# SCFschem.net
KiCad netlist of a schematic drawn in EAGLE
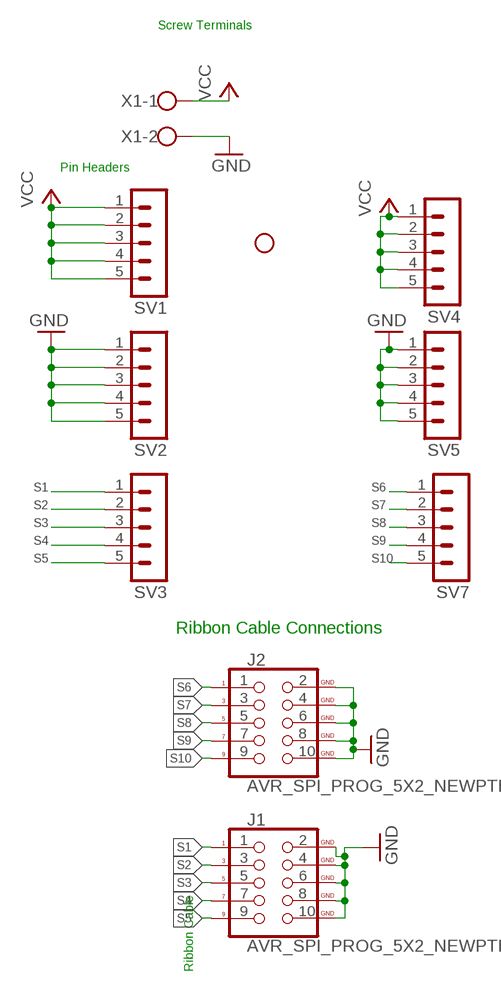
[diagram p0: schematic, sheet 1]

(export (version "E")
  (design (tool "Eeschema 10.0.6"))
  (components
    (comp (ref "H1")
      (value "STAND-OFF")
      (footprint "eagle-import:STAND-OFF")
      (libsource (lib "eagle-import") (part "STAND-OFF"))
    )
    (comp (ref "J1")
      (value "AVR_SPI_PROG_5X2_NEWPTH2")
      (footprint "eagle-import:2X5-SHROUDED")
      (libsource (lib "eagle-import") (part "AVR_SPI_PROG_5X2_NEWPTH2"))
    )
    (comp (ref "J2")
      (value "AVR_SPI_PROG_5X2_NEWPTH2")
      (footprint "eagle-import:2X5-SHROUDED")
      (libsource (lib "eagle-import") (part "AVR_SPI_PROG_5X2_NEWPTH2"))
    )
    (comp (ref "SV1")
      (value "MA05-1")
      (footprint "eagle-import:MA05-1")
      (libsource (lib "eagle-import") (part "MA05-1"))
    )
    (comp (ref "SV2")
      (value "MA05-1")
      (footprint "eagle-import:MA05-1")
      (libsource (lib "eagle-import") (part "MA05-1"))
    )
    (comp (ref "SV3")
      (value "MA05-1")
      (footprint "eagle-import:MA05-1")
      (libsource (lib "eagle-import") (part "MA05-1"))
    )
    (comp (ref "SV4")
      (value "MA05-1")
      (footprint "eagle-import:MA05-1")
      (libsource (lib "eagle-import") (part "MA05-1"))
    )
    (comp (ref "SV5")
      (value "MA05-1")
      (footprint "eagle-import:MA05-1")
      (libsource (lib "eagle-import") (part "MA05-1"))
    )
    (comp (ref "SV7")
      (value "MA05-1")
      (footprint "eagle-import:MA05-1")
      (libsource (lib "eagle-import") (part "MA05-1"))
    )
    (comp (ref "X1")
      (value "1X02_5MM_SCREW")
      (footprint "eagle-import:W237-102")
      (fields (field (name "MPN") "237-102"))
      (libsource (lib "eagle-import") (part "1X02_5MM_SCREW"))
    )
  )
  (nets
    (net (code "1") (name "GND") (class "Default")
      (node (ref "J1") (pin "10") (pinfunction "GND_10") (pintype "power_in"))
      (node (ref "J1") (pin "2") (pinfunction "GND_2") (pintype "power_in"))
      (node (ref "J1") (pin "4") (pinfunction "GND_4") (pintype "power_in"))
      (node (ref "J1") (pin "6") (pinfunction "GND_6") (pintype "power_in"))
      (node (ref "J1") (pin "8") (pinfunction "GND_8") (pintype "power_in"))
      (node (ref "J2") (pin "10") (pinfunction "GND_10") (pintype "power_in"))
      (node (ref "J2") (pin "2") (pinfunction "GND_2") (pintype "power_in"))
      (node (ref "J2") (pin "4") (pinfunction "GND_4") (pintype "power_in"))
      (node (ref "J2") (pin "6") (pinfunction "GND_6") (pintype "power_in"))
      (node (ref "J2") (pin "8") (pinfunction "GND_8") (pintype "power_in"))
      (node (ref "SV2") (pin "1") (pinfunction "1_1") (pintype "passive"))
      (node (ref "SV2") (pin "2") (pinfunction "2_2") (pintype "passive"))
      (node (ref "SV2") (pin "3") (pinfunction "3_3") (pintype "passive"))
      (node (ref "SV2") (pin "4") (pinfunction "4_4") (pintype "passive"))
      (node (ref "SV2") (pin "5") (pinfunction "5_5") (pintype "passive"))
      (node (ref "SV5") (pin "1") (pinfunction "1_1") (pintype "passive"))
      (node (ref "SV5") (pin "2") (pinfunction "2_2") (pintype "passive"))
      (node (ref "SV5") (pin "3") (pinfunction "3_3") (pintype "passive"))
      (node (ref "SV5") (pin "4") (pinfunction "4_4") (pintype "passive"))
      (node (ref "SV5") (pin "5") (pinfunction "5_5") (pintype "passive"))
      (node (ref "X1") (pin "2") (pinfunction "KL_2") (pintype "passive"))
    )
    (net (code "2") (name "S1") (class "Default")
      (node (ref "J1") (pin "1") (pinfunction "1_1") (pintype "passive"))
      (node (ref "SV3") (pin "1") (pinfunction "1_1") (pintype "passive"))
    )
    (net (code "3") (name "S2") (class "Default")
      (node (ref "J1") (pin "3") (pinfunction "3_3") (pintype "passive"))
      (node (ref "SV3") (pin "2") (pinfunction "2_2") (pintype "passive"))
    )
    (net (code "4") (name "S3") (class "Default")
      (node (ref "J1") (pin "5") (pinfunction "5_5") (pintype "passive"))
      (node (ref "SV3") (pin "3") (pinfunction "3_3") (pintype "passive"))
    )
    (net (code "5") (name "S4") (class "Default")
      (node (ref "J1") (pin "7") (pinfunction "7_7") (pintype "passive"))
      (node (ref "SV3") (pin "4") (pinfunction "4_4") (pintype "passive"))
    )
    (net (code "6") (name "S5") (class "Default")
      (node (ref "J1") (pin "9") (pinfunction "9_9") (pintype "passive"))
      (node (ref "SV3") (pin "5") (pinfunction "5_5") (pintype "passive"))
    )
    (net (code "7") (name "S6") (class "Default")
      (node (ref "J2") (pin "1") (pinfunction "1_1") (pintype "passive"))
      (node (ref "SV7") (pin "1") (pinfunction "1_1") (pintype "passive"))
    )
    (net (code "8") (name "S7") (class "Default")
      (node (ref "J2") (pin "3") (pinfunction "3_3") (pintype "passive"))
      (node (ref "SV7") (pin "2") (pinfunction "2_2") (pintype "passive"))
    )
    (net (code "9") (name "S8") (class "Default")
      (node (ref "J2") (pin "5") (pinfunction "5_5") (pintype "passive"))
      (node (ref "SV7") (pin "3") (pinfunction "3_3") (pintype "passive"))
    )
    (net (code "10") (name "S9") (class "Default")
      (node (ref "J2") (pin "7") (pinfunction "7_7") (pintype "passive"))
      (node (ref "SV7") (pin "4") (pinfunction "4_4") (pintype "passive"))
    )
    (net (code "11") (name "S10") (class "Default")
      (node (ref "J2") (pin "9") (pinfunction "9_9") (pintype "passive"))
      (node (ref "SV7") (pin "5") (pinfunction "5_5") (pintype "passive"))
    )
    (net (code "12") (name "VCC") (class "Default")
      (node (ref "SV1") (pin "1") (pinfunction "1_1") (pintype "passive"))
      (node (ref "SV1") (pin "2") (pinfunction "2_2") (pintype "passive"))
      (node (ref "SV1") (pin "3") (pinfunction "3_3") (pintype "passive"))
      (node (ref "SV1") (pin "4") (pinfunction "4_4") (pintype "passive"))
      (node (ref "SV1") (pin "5") (pinfunction "5_5") (pintype "passive"))
      (node (ref "SV4") (pin "1") (pinfunction "1_1") (pintype "passive"))
      (node (ref "SV4") (pin "2") (pinfunction "2_2") (pintype "passive"))
      (node (ref "SV4") (pin "3") (pinfunction "3_3") (pintype "passive"))
      (node (ref "SV4") (pin "4") (pinfunction "4_4") (pintype "passive"))
      (node (ref "SV4") (pin "5") (pinfunction "5_5") (pintype "passive"))
      (node (ref "X1") (pin "1") (pinfunction "KL_1") (pintype "passive"))
    )
  )
)
